# Rev_A.net
KiCad netlist of a schematic drawn in EAGLE
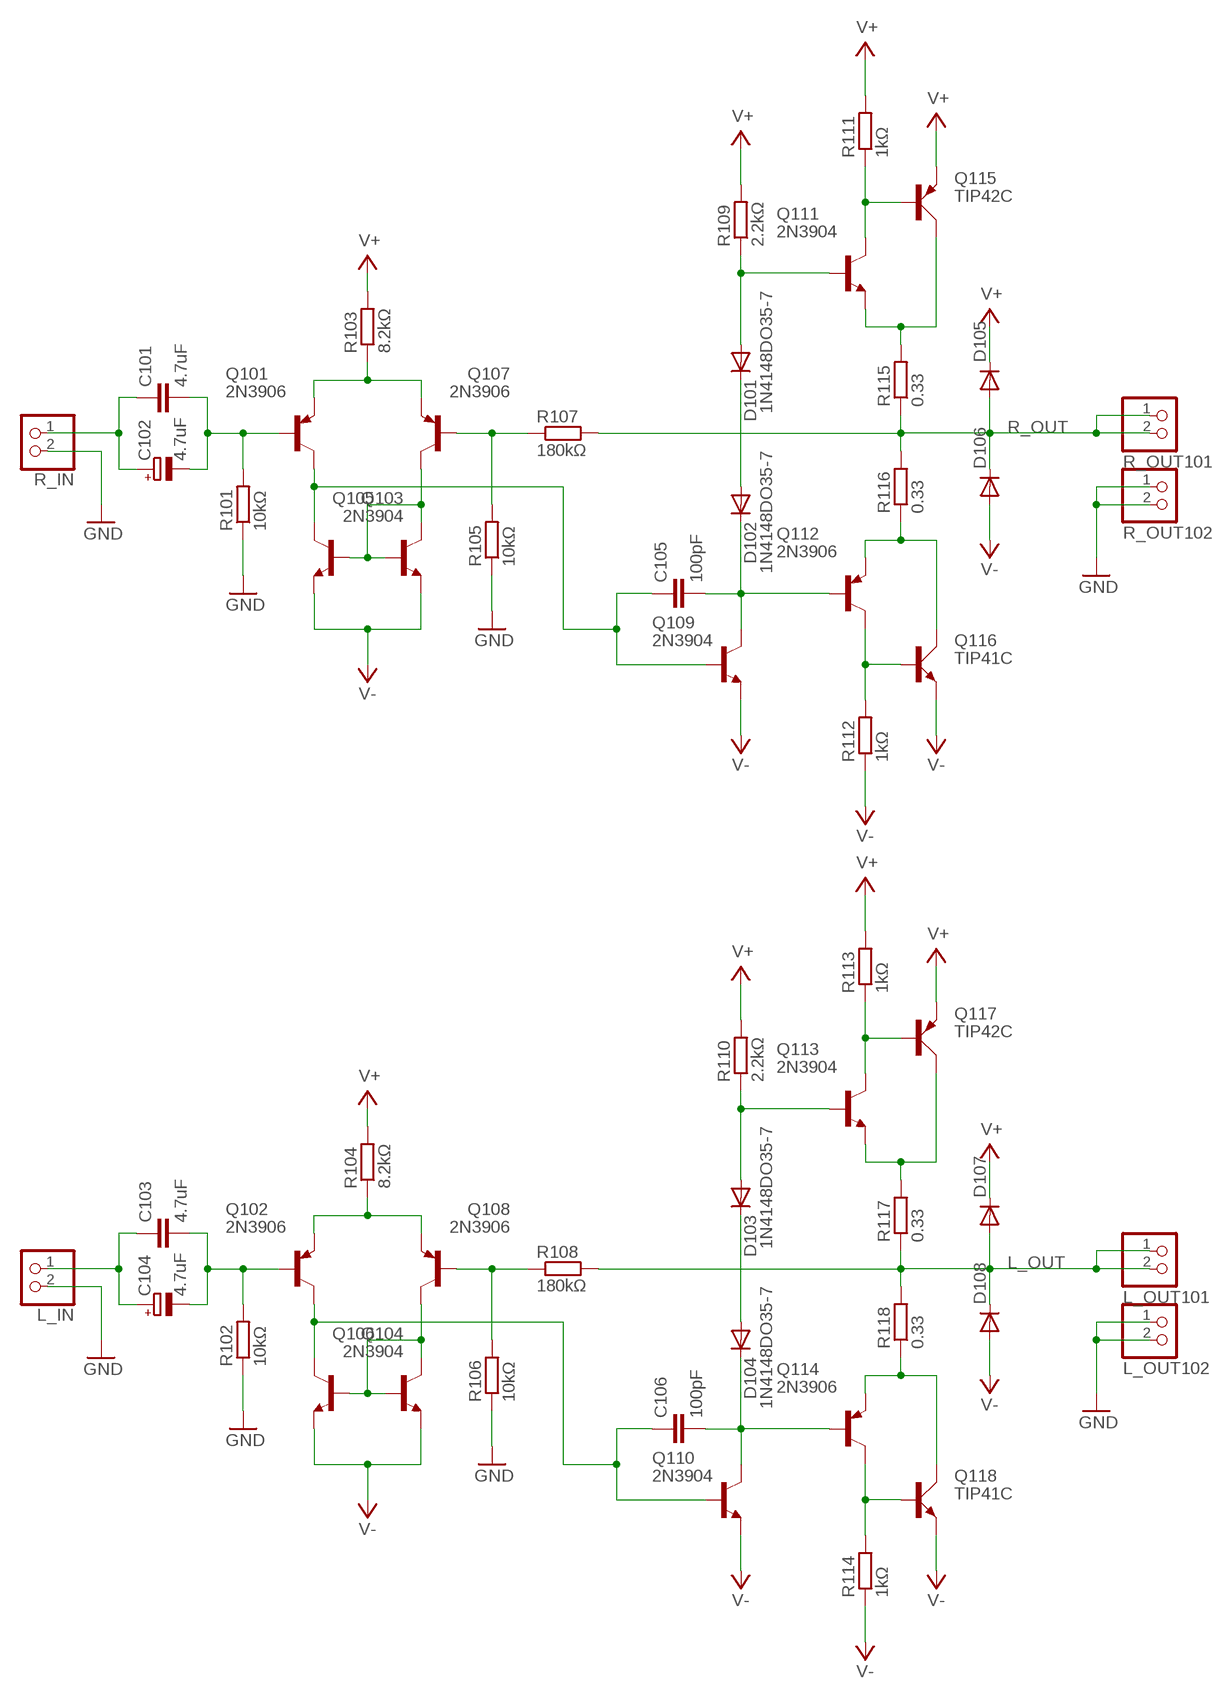
[diagram p0: schematic, sheet 1]
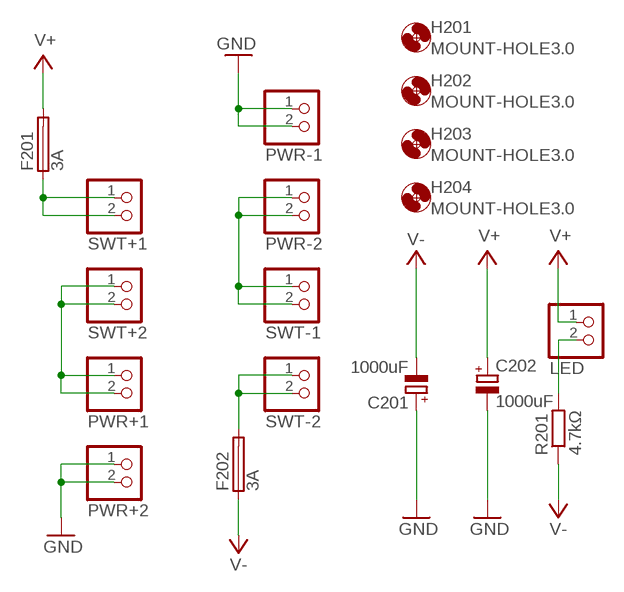
[diagram p1: schematic, sheet 2]

(export (version "E")
  (design (tool "Eeschema 10.0.6"))
  (components
    (comp (ref "C101")
      (value "4.7uF")
      (footprint "eagle-import:C225-113X268")
      (libsource (lib "eagle-import") (part "C-EU225-113X268"))
    )
    (comp (ref "C102")
      (value "4.7uF")
      (footprint "eagle-import:E2-5")
      (libsource (lib "eagle-import") (part "CPOL-EUE2-5"))
    )
    (comp (ref "C103")
      (value "4.7uF")
      (footprint "eagle-import:C225-113X268")
      (libsource (lib "eagle-import") (part "C-EU225-113X268"))
    )
    (comp (ref "C104")
      (value "4.7uF")
      (footprint "eagle-import:E2-5")
      (libsource (lib "eagle-import") (part "CPOL-EUE2-5"))
    )
    (comp (ref "C105")
      (value "100pF")
      (footprint "eagle-import:C050-050X075")
      (libsource (lib "eagle-import") (part "C-EU050-050X075"))
    )
    (comp (ref "C106")
      (value "100pF")
      (footprint "eagle-import:C050-050X075")
      (libsource (lib "eagle-import") (part "C-EU050-050X075"))
    )
    (comp (ref "D101")
      (value "1N4148DO35-7")
      (footprint "eagle-import:DO35-7")
      (libsource (lib "eagle-import") (part "1N4148DO35-7"))
    )
    (comp (ref "D102")
      (value "1N4148DO35-7")
      (footprint "eagle-import:DO35-7")
      (libsource (lib "eagle-import") (part "1N4148DO35-7"))
    )
    (comp (ref "D103")
      (value "1N4148DO35-7")
      (footprint "eagle-import:DO35-7")
      (libsource (lib "eagle-import") (part "1N4148DO35-7"))
    )
    (comp (ref "D104")
      (value "1N4148DO35-7")
      (footprint "eagle-import:DO35-7")
      (libsource (lib "eagle-import") (part "1N4148DO35-7"))
    )
    (comp (ref "D105")
      (value "1N4148DO35-7")
      (footprint "eagle-import:DO35-7")
      (libsource (lib "eagle-import") (part "1N4148DO35-7"))
    )
    (comp (ref "D106")
      (value "1N4148DO35-7")
      (footprint "eagle-import:DO35-7")
      (libsource (lib "eagle-import") (part "1N4148DO35-7"))
    )
    (comp (ref "D107")
      (value "1N4148DO35-7")
      (footprint "eagle-import:DO35-7")
      (libsource (lib "eagle-import") (part "1N4148DO35-7"))
    )
    (comp (ref "D108")
      (value "1N4148DO35-7")
      (footprint "eagle-import:DO35-7")
      (libsource (lib "eagle-import") (part "1N4148DO35-7"))
    )
    (comp (ref "L_IN")
      (value "JST_2PIN-THM")
      (footprint "eagle-import:JST-PH-2-THM")
      (libsource (lib "eagle-import") (part "JST_2PIN-THM"))
    )
    (comp (ref "L_OUT101")
      (value "JST_2PIN-THM")
      (footprint "eagle-import:JST-PH-2-THM")
      (libsource (lib "eagle-import") (part "JST_2PIN-THM"))
    )
    (comp (ref "L_OUT102")
      (value "JST_2PIN-THM")
      (footprint "eagle-import:JST-PH-2-THM")
      (libsource (lib "eagle-import") (part "JST_2PIN-THM"))
    )
    (comp (ref "Q101")
      (value "2N3906")
      (footprint "eagle-import:TO92")
      (libsource (lib "eagle-import") (part "2N3906"))
    )
    (comp (ref "Q102")
      (value "2N3906")
      (footprint "eagle-import:TO92")
      (libsource (lib "eagle-import") (part "2N3906"))
    )
    (comp (ref "Q103")
      (value "2N3904")
      (footprint "eagle-import:TO92")
      (libsource (lib "eagle-import") (part "2N3904"))
    )
    (comp (ref "Q104")
      (value "2N3904")
      (footprint "eagle-import:TO92")
      (libsource (lib "eagle-import") (part "2N3904"))
    )
    (comp (ref "Q105")
      (value "2N3904")
      (footprint "eagle-import:TO92")
      (libsource (lib "eagle-import") (part "2N3904"))
    )
    (comp (ref "Q106")
      (value "2N3904")
      (footprint "eagle-import:TO92")
      (libsource (lib "eagle-import") (part "2N3904"))
    )
    (comp (ref "Q107")
      (value "2N3906")
      (footprint "eagle-import:TO92")
      (libsource (lib "eagle-import") (part "2N3906"))
    )
    (comp (ref "Q108")
      (value "2N3906")
      (footprint "eagle-import:TO92")
      (libsource (lib "eagle-import") (part "2N3906"))
    )
    (comp (ref "Q109")
      (value "2N3904")
      (footprint "eagle-import:TO92")
      (libsource (lib "eagle-import") (part "2N3904"))
    )
    (comp (ref "Q110")
      (value "2N3904")
      (footprint "eagle-import:TO92")
      (libsource (lib "eagle-import") (part "2N3904"))
    )
    (comp (ref "Q111")
      (value "2N3904")
      (footprint "eagle-import:TO92")
      (libsource (lib "eagle-import") (part "2N3904"))
    )
    (comp (ref "Q112")
      (value "2N3906")
      (footprint "eagle-import:TO92")
      (libsource (lib "eagle-import") (part "2N3906"))
    )
    (comp (ref "Q113")
      (value "2N3904")
      (footprint "eagle-import:TO92")
      (libsource (lib "eagle-import") (part "2N3904"))
    )
    (comp (ref "Q114")
      (value "2N3906")
      (footprint "eagle-import:TO92")
      (libsource (lib "eagle-import") (part "2N3906"))
    )
    (comp (ref "Q115")
      (value "TIP42C")
      (footprint "eagle-import:TO220AV")
      (libsource (lib "eagle-import") (part "TIP42C"))
    )
    (comp (ref "Q116")
      (value "TIP41C")
      (footprint "eagle-import:TO220AV")
      (libsource (lib "eagle-import") (part "TIP41C"))
    )
    (comp (ref "Q117")
      (value "TIP42C")
      (footprint "eagle-import:TO220AV")
      (libsource (lib "eagle-import") (part "TIP42C"))
    )
    (comp (ref "Q118")
      (value "TIP41C")
      (footprint "eagle-import:TO220AV")
      (libsource (lib "eagle-import") (part "TIP41C"))
    )
    (comp (ref "R101")
      (value "10kΩ")
      (footprint "eagle-import:0207_10")
      (libsource (lib "eagle-import") (part "R-EU_0207/10"))
    )
    (comp (ref "R102")
      (value "10kΩ")
      (footprint "eagle-import:0207_10")
      (libsource (lib "eagle-import") (part "R-EU_0207/10"))
    )
    (comp (ref "R103")
      (value "8.2kΩ")
      (footprint "eagle-import:0207_10")
      (libsource (lib "eagle-import") (part "R-EU_0207/10"))
    )
    (comp (ref "R104")
      (value "8.2kΩ")
      (footprint "eagle-import:0207_10")
      (libsource (lib "eagle-import") (part "R-EU_0207/10"))
    )
    (comp (ref "R105")
      (value "10kΩ")
      (footprint "eagle-import:0207_10")
      (libsource (lib "eagle-import") (part "R-EU_0207/10"))
    )
    (comp (ref "R106")
      (value "10kΩ")
      (footprint "eagle-import:0207_10")
      (libsource (lib "eagle-import") (part "R-EU_0207/10"))
    )
    (comp (ref "R107")
      (value "180kΩ")
      (footprint "eagle-import:0207_10")
      (libsource (lib "eagle-import") (part "R-EU_0207/10"))
    )
    (comp (ref "R108")
      (value "180kΩ")
      (footprint "eagle-import:0207_10")
      (libsource (lib "eagle-import") (part "R-EU_0207/10"))
    )
    (comp (ref "R109")
      (value "2.2kΩ")
      (footprint "eagle-import:0207_10")
      (libsource (lib "eagle-import") (part "R-EU_0207/10"))
    )
    (comp (ref "R110")
      (value "2.2kΩ")
      (footprint "eagle-import:0207_10")
      (libsource (lib "eagle-import") (part "R-EU_0207/10"))
    )
    (comp (ref "R111")
      (value "1kΩ")
      (footprint "eagle-import:0207_10")
      (libsource (lib "eagle-import") (part "R-EU_0207/10"))
    )
    (comp (ref "R112")
      (value "1kΩ")
      (footprint "eagle-import:0207_10")
      (libsource (lib "eagle-import") (part "R-EU_0207/10"))
    )
    (comp (ref "R113")
      (value "1kΩ")
      (footprint "eagle-import:0207_10")
      (libsource (lib "eagle-import") (part "R-EU_0207/10"))
    )
    (comp (ref "R114")
      (value "1kΩ")
      (footprint "eagle-import:0207_10")
      (libsource (lib "eagle-import") (part "R-EU_0207/10"))
    )
    (comp (ref "R115")
      (value "0.33")
      (footprint "eagle-import:0414_15")
      (libsource (lib "eagle-import") (part "R-EU_0414/15"))
    )
    (comp (ref "R116")
      (value "0.33")
      (footprint "eagle-import:0414_15")
      (libsource (lib "eagle-import") (part "R-EU_0414/15"))
    )
    (comp (ref "R117")
      (value "0.33")
      (footprint "eagle-import:0414_15")
      (libsource (lib "eagle-import") (part "R-EU_0414/15"))
    )
    (comp (ref "R118")
      (value "0.33")
      (footprint "eagle-import:0414_15")
      (libsource (lib "eagle-import") (part "R-EU_0414/15"))
    )
    (comp (ref "R_IN")
      (value "JST_2PIN-THM")
      (footprint "eagle-import:JST-PH-2-THM")
      (libsource (lib "eagle-import") (part "JST_2PIN-THM"))
    )
    (comp (ref "R_OUT101")
      (value "JST_2PIN-THM")
      (footprint "eagle-import:JST-PH-2-THM")
      (libsource (lib "eagle-import") (part "JST_2PIN-THM"))
    )
    (comp (ref "R_OUT102")
      (value "JST_2PIN-THM")
      (footprint "eagle-import:JST-PH-2-THM")
      (libsource (lib "eagle-import") (part "JST_2PIN-THM"))
    )
    (comp (ref "C201")
      (value "1000uF")
      (footprint "eagle-import:E5-10,5")
      (libsource (lib "eagle-import") (part "CPOL-EUE5-10.5"))
    )
    (comp (ref "C202")
      (value "1000uF")
      (footprint "eagle-import:E5-10,5")
      (libsource (lib "eagle-import") (part "CPOL-EUE5-10.5"))
    )
    (comp (ref "F201")
      (value "3A")
      (footprint "eagle-import:SH22,5")
      (fields (field (name "MF") "SCHURTER") (field (name "MPN") "0031.8201"))
      (libsource (lib "eagle-import") (part "SH22,5"))
    )
    (comp (ref "F202")
      (value "3A")
      (footprint "eagle-import:SH22,5")
      (fields (field (name "MF") "SCHURTER") (field (name "MPN") "0031.8201"))
      (libsource (lib "eagle-import") (part "SH22,5"))
    )
    (comp (ref "H201")
      (value "MOUNT-HOLE3.0")
      (footprint "eagle-import:3,0")
      (libsource (lib "eagle-import") (part "MOUNT-HOLE3.0"))
    )
    (comp (ref "H202")
      (value "MOUNT-HOLE3.0")
      (footprint "eagle-import:3,0")
      (libsource (lib "eagle-import") (part "MOUNT-HOLE3.0"))
    )
    (comp (ref "H203")
      (value "MOUNT-HOLE3.0")
      (footprint "eagle-import:3,0")
      (libsource (lib "eagle-import") (part "MOUNT-HOLE3.0"))
    )
    (comp (ref "H204")
      (value "MOUNT-HOLE3.0")
      (footprint "eagle-import:3,0")
      (libsource (lib "eagle-import") (part "MOUNT-HOLE3.0"))
    )
    (comp (ref "LED")
      (value "JST_2PIN-THM")
      (footprint "eagle-import:JST-PH-2-THM")
      (libsource (lib "eagle-import") (part "JST_2PIN-THM"))
    )
    (comp (ref "PWR+1")
      (value "JST_2PIN-THM")
      (footprint "eagle-import:JST-PH-2-THM")
      (libsource (lib "eagle-import") (part "JST_2PIN-THM"))
    )
    (comp (ref "PWR+2")
      (value "JST_2PIN-THM")
      (footprint "eagle-import:JST-PH-2-THM")
      (libsource (lib "eagle-import") (part "JST_2PIN-THM"))
    )
    (comp (ref "PWR-1")
      (value "JST_2PIN-THM")
      (footprint "eagle-import:JST-PH-2-THM")
      (libsource (lib "eagle-import") (part "JST_2PIN-THM"))
    )
    (comp (ref "PWR-2")
      (value "JST_2PIN-THM")
      (footprint "eagle-import:JST-PH-2-THM")
      (libsource (lib "eagle-import") (part "JST_2PIN-THM"))
    )
    (comp (ref "R201")
      (value "4.7kΩ")
      (footprint "eagle-import:0207_10")
      (libsource (lib "eagle-import") (part "R-EU_0207/10"))
    )
    (comp (ref "SWT+1")
      (value "JST_2PIN-THM")
      (footprint "eagle-import:JST-PH-2-THM")
      (libsource (lib "eagle-import") (part "JST_2PIN-THM"))
    )
    (comp (ref "SWT+2")
      (value "JST_2PIN-THM")
      (footprint "eagle-import:JST-PH-2-THM")
      (libsource (lib "eagle-import") (part "JST_2PIN-THM"))
    )
    (comp (ref "SWT-1")
      (value "JST_2PIN-THM")
      (footprint "eagle-import:JST-PH-2-THM")
      (libsource (lib "eagle-import") (part "JST_2PIN-THM"))
    )
    (comp (ref "SWT-2")
      (value "JST_2PIN-THM")
      (footprint "eagle-import:JST-PH-2-THM")
      (libsource (lib "eagle-import") (part "JST_2PIN-THM"))
    )
  )
  (nets
    (net (code "1") (name "GND") (class "Default")
      (node (ref "C201") (pin "+") (pinfunction "+_+") (pintype "passive"))
      (node (ref "C202") (pin "-") (pinfunction "-_-") (pintype "passive"))
      (node (ref "L_IN") (pin "2") (pinfunction "1_2") (pintype "passive"))
      (node (ref "L_OUT102") (pin "1") (pinfunction "2_1") (pintype "passive"))
      (node (ref "L_OUT102") (pin "2") (pinfunction "1_2") (pintype "passive"))
      (node (ref "PWR+2") (pin "1") (pinfunction "2_1") (pintype "passive"))
      (node (ref "PWR+2") (pin "2") (pinfunction "1_2") (pintype "passive"))
      (node (ref "PWR-1") (pin "1") (pinfunction "2_1") (pintype "passive"))
      (node (ref "PWR-1") (pin "2") (pinfunction "1_2") (pintype "passive"))
      (node (ref "R101") (pin "1") (pinfunction "1_1") (pintype "passive"))
      (node (ref "R102") (pin "1") (pinfunction "1_1") (pintype "passive"))
      (node (ref "R105") (pin "1") (pinfunction "1_1") (pintype "passive"))
      (node (ref "R106") (pin "1") (pinfunction "1_1") (pintype "passive"))
      (node (ref "R_IN") (pin "2") (pinfunction "1_2") (pintype "passive"))
      (node (ref "R_OUT102") (pin "1") (pinfunction "2_1") (pintype "passive"))
      (node (ref "R_OUT102") (pin "2") (pinfunction "1_2") (pintype "passive"))
    )
    (net (code "2") (name "L_OUT") (class "Default")
      (node (ref "D107") (pin "A") (pinfunction "A_A") (pintype "passive"))
      (node (ref "D108") (pin "C") (pinfunction "C_C") (pintype "passive"))
      (node (ref "L_OUT101") (pin "1") (pinfunction "2_1") (pintype "passive"))
      (node (ref "L_OUT101") (pin "2") (pinfunction "1_2") (pintype "passive"))
      (node (ref "R108") (pin "2") (pinfunction "2_2") (pintype "passive"))
      (node (ref "R117") (pin "1") (pinfunction "1_1") (pintype "passive"))
      (node (ref "R118") (pin "2") (pinfunction "2_2") (pintype "passive"))
    )
    (net (code "3") (name "Net-(D101-PadC)") (class "Default")
      (node (ref "D101") (pin "C") (pinfunction "C_C") (pintype "passive"))
      (node (ref "D102") (pin "A") (pinfunction "A_A") (pintype "passive"))
    )
    (net (code "4") (name "Net-(D103-PadC)") (class "Default")
      (node (ref "D103") (pin "C") (pinfunction "C_C") (pintype "passive"))
      (node (ref "D104") (pin "A") (pinfunction "A_A") (pintype "passive"))
    )
    (net (code "5") (name "Net-(LED-1)") (class "Default")
      (node (ref "LED") (pin "2") (pinfunction "1_2") (pintype "passive"))
      (node (ref "R201") (pin "2") (pinfunction "2_2") (pintype "passive"))
    )
    (net (code "6") (name "Net-(L_IN-2)") (class "Default")
      (node (ref "C103") (pin "1") (pinfunction "1_1") (pintype "passive"))
      (node (ref "C104") (pin "+") (pinfunction "+_+") (pintype "passive"))
      (node (ref "L_IN") (pin "1") (pinfunction "2_1") (pintype "passive"))
    )
    (net (code "7") (name "Net-(PWR+1-1)") (class "Default")
      (node (ref "PWR+1") (pin "1") (pinfunction "2_1") (pintype "passive"))
      (node (ref "PWR+1") (pin "2") (pinfunction "1_2") (pintype "passive"))
      (node (ref "SWT+2") (pin "1") (pinfunction "2_1") (pintype "passive"))
      (node (ref "SWT+2") (pin "2") (pinfunction "1_2") (pintype "passive"))
    )
    (net (code "8") (name "Net-(PWR-2-1)") (class "Default")
      (node (ref "PWR-2") (pin "1") (pinfunction "2_1") (pintype "passive"))
      (node (ref "PWR-2") (pin "2") (pinfunction "1_2") (pintype "passive"))
      (node (ref "SWT-1") (pin "1") (pinfunction "2_1") (pintype "passive"))
      (node (ref "SWT-1") (pin "2") (pinfunction "1_2") (pintype "passive"))
    )
    (net (code "9") (name "Net-(Q101-B)") (class "Default")
      (node (ref "C101") (pin "2") (pinfunction "2_2") (pintype "passive"))
      (node (ref "C102") (pin "-") (pinfunction "-_-") (pintype "passive"))
      (node (ref "Q101") (pin "2") (pinfunction "B_2") (pintype "passive"))
      (node (ref "R101") (pin "2") (pinfunction "2_2") (pintype "passive"))
    )
    (net (code "10") (name "Net-(Q101-C)") (class "Default")
      (node (ref "C105") (pin "1") (pinfunction "1_1") (pintype "passive"))
      (node (ref "Q101") (pin "1") (pinfunction "C_1") (pintype "passive"))
      (node (ref "Q103") (pin "1") (pinfunction "C_1") (pintype "passive"))
      (node (ref "Q109") (pin "2") (pinfunction "B_2") (pintype "passive"))
    )
    (net (code "11") (name "Net-(Q101-E)") (class "Default")
      (node (ref "Q101") (pin "3") (pinfunction "E_3") (pintype "passive"))
      (node (ref "Q107") (pin "3") (pinfunction "E_3") (pintype "passive"))
      (node (ref "R103") (pin "1") (pinfunction "1_1") (pintype "passive"))
    )
    (net (code "12") (name "Net-(Q102-B)") (class "Default")
      (node (ref "C103") (pin "2") (pinfunction "2_2") (pintype "passive"))
      (node (ref "C104") (pin "-") (pinfunction "-_-") (pintype "passive"))
      (node (ref "Q102") (pin "2") (pinfunction "B_2") (pintype "passive"))
      (node (ref "R102") (pin "2") (pinfunction "2_2") (pintype "passive"))
    )
    (net (code "13") (name "Net-(Q102-C)") (class "Default")
      (node (ref "C106") (pin "1") (pinfunction "1_1") (pintype "passive"))
      (node (ref "Q102") (pin "1") (pinfunction "C_1") (pintype "passive"))
      (node (ref "Q104") (pin "1") (pinfunction "C_1") (pintype "passive"))
      (node (ref "Q110") (pin "2") (pinfunction "B_2") (pintype "passive"))
    )
    (net (code "14") (name "Net-(Q102-E)") (class "Default")
      (node (ref "Q102") (pin "3") (pinfunction "E_3") (pintype "passive"))
      (node (ref "Q108") (pin "3") (pinfunction "E_3") (pintype "passive"))
      (node (ref "R104") (pin "1") (pinfunction "1_1") (pintype "passive"))
    )
    (net (code "15") (name "Net-(Q103-B)") (class "Default")
      (node (ref "Q103") (pin "2") (pinfunction "B_2") (pintype "passive"))
      (node (ref "Q105") (pin "1") (pinfunction "C_1") (pintype "passive"))
      (node (ref "Q105") (pin "2") (pinfunction "B_2") (pintype "passive"))
      (node (ref "Q107") (pin "1") (pinfunction "C_1") (pintype "passive"))
    )
    (net (code "16") (name "Net-(Q104-B)") (class "Default")
      (node (ref "Q104") (pin "2") (pinfunction "B_2") (pintype "passive"))
      (node (ref "Q106") (pin "1") (pinfunction "C_1") (pintype "passive"))
      (node (ref "Q106") (pin "2") (pinfunction "B_2") (pintype "passive"))
      (node (ref "Q108") (pin "1") (pinfunction "C_1") (pintype "passive"))
    )
    (net (code "17") (name "Net-(Q107-B)") (class "Default")
      (node (ref "Q107") (pin "2") (pinfunction "B_2") (pintype "passive"))
      (node (ref "R105") (pin "2") (pinfunction "2_2") (pintype "passive"))
      (node (ref "R107") (pin "1") (pinfunction "1_1") (pintype "passive"))
    )
    (net (code "18") (name "Net-(Q108-B)") (class "Default")
      (node (ref "Q108") (pin "2") (pinfunction "B_2") (pintype "passive"))
      (node (ref "R106") (pin "2") (pinfunction "2_2") (pintype "passive"))
      (node (ref "R108") (pin "1") (pinfunction "1_1") (pintype "passive"))
    )
    (net (code "19") (name "Net-(Q109-C)") (class "Default")
      (node (ref "C105") (pin "2") (pinfunction "2_2") (pintype "passive"))
      (node (ref "D102") (pin "C") (pinfunction "C_C") (pintype "passive"))
      (node (ref "Q109") (pin "1") (pinfunction "C_1") (pintype "passive"))
      (node (ref "Q112") (pin "2") (pinfunction "B_2") (pintype "passive"))
    )
    (net (code "20") (name "Net-(Q110-C)") (class "Default")
      (node (ref "C106") (pin "2") (pinfunction "2_2") (pintype "passive"))
      (node (ref "D104") (pin "C") (pinfunction "C_C") (pintype "passive"))
      (node (ref "Q110") (pin "1") (pinfunction "C_1") (pintype "passive"))
      (node (ref "Q114") (pin "2") (pinfunction "B_2") (pintype "passive"))
    )
    (net (code "21") (name "Net-(Q111-B)") (class "Default")
      (node (ref "D101") (pin "A") (pinfunction "A_A") (pintype "passive"))
      (node (ref "Q111") (pin "2") (pinfunction "B_2") (pintype "passive"))
      (node (ref "R109") (pin "1") (pinfunction "1_1") (pintype "passive"))
    )
    (net (code "22") (name "Net-(Q111-C)") (class "Default")
      (node (ref "Q111") (pin "1") (pinfunction "C_1") (pintype "passive"))
      (node (ref "Q115") (pin "B") (pinfunction "B_B") (pintype "passive"))
      (node (ref "R111") (pin "1") (pinfunction "1_1") (pintype "passive"))
    )
    (net (code "23") (name "Net-(Q111-E)") (class "Default")
      (node (ref "Q111") (pin "3") (pinfunction "E_3") (pintype "passive"))
      (node (ref "Q115") (pin "C") (pinfunction "C_C") (pintype "passive"))
      (node (ref "R115") (pin "2") (pinfunction "2_2") (pintype "passive"))
    )
    (net (code "24") (name "Net-(Q112-C)") (class "Default")
      (node (ref "Q112") (pin "1") (pinfunction "C_1") (pintype "passive"))
      (node (ref "Q116") (pin "B") (pinfunction "B_B") (pintype "passive"))
      (node (ref "R112") (pin "2") (pinfunction "2_2") (pintype "passive"))
    )
    (net (code "25") (name "Net-(Q112-E)") (class "Default")
      (node (ref "Q112") (pin "3") (pinfunction "E_3") (pintype "passive"))
      (node (ref "Q116") (pin "C") (pinfunction "C_C") (pintype "passive"))
      (node (ref "R116") (pin "1") (pinfunction "1_1") (pintype "passive"))
    )
    (net (code "26") (name "Net-(Q113-B)") (class "Default")
      (node (ref "D103") (pin "A") (pinfunction "A_A") (pintype "passive"))
      (node (ref "Q113") (pin "2") (pinfunction "B_2") (pintype "passive"))
      (node (ref "R110") (pin "1") (pinfunction "1_1") (pintype "passive"))
    )
    (net (code "27") (name "Net-(Q113-C)") (class "Default")
      (node (ref "Q113") (pin "1") (pinfunction "C_1") (pintype "passive"))
      (node (ref "Q117") (pin "B") (pinfunction "B_B") (pintype "passive"))
      (node (ref "R113") (pin "1") (pinfunction "1_1") (pintype "passive"))
    )
    (net (code "28") (name "Net-(Q113-E)") (class "Default")
      (node (ref "Q113") (pin "3") (pinfunction "E_3") (pintype "passive"))
      (node (ref "Q117") (pin "C") (pinfunction "C_C") (pintype "passive"))
      (node (ref "R117") (pin "2") (pinfunction "2_2") (pintype "passive"))
    )
    (net (code "29") (name "Net-(Q114-C)") (class "Default")
      (node (ref "Q114") (pin "1") (pinfunction "C_1") (pintype "passive"))
      (node (ref "Q118") (pin "B") (pinfunction "B_B") (pintype "passive"))
      (node (ref "R114") (pin "2") (pinfunction "2_2") (pintype "passive"))
    )
    (net (code "30") (name "Net-(Q114-E)") (class "Default")
      (node (ref "Q114") (pin "3") (pinfunction "E_3") (pintype "passive"))
      (node (ref "Q118") (pin "C") (pinfunction "C_C") (pintype "passive"))
      (node (ref "R118") (pin "1") (pinfunction "1_1") (pintype "passive"))
    )
    (net (code "31") (name "Net-(R_IN-2)") (class "Default")
      (node (ref "C101") (pin "1") (pinfunction "1_1") (pintype "passive"))
      (node (ref "C102") (pin "+") (pinfunction "+_+") (pintype "passive"))
      (node (ref "R_IN") (pin "1") (pinfunction "2_1") (pintype "passive"))
    )
    (net (code "32") (name "Net-(SWT+1-1)") (class "Default")
      (node (ref "F201") (pin "1") (pinfunction "1_1") (pintype "passive"))
      (node (ref "SWT+1") (pin "1") (pinfunction "2_1") (pintype "passive"))
      (node (ref "SWT+1") (pin "2") (pinfunction "1_2") (pintype "passive"))
    )
    (net (code "33") (name "Net-(SWT-2-1)") (class "Default")
      (node (ref "F202") (pin "2") (pinfunction "2_2") (pintype "passive"))
      (node (ref "SWT-2") (pin "1") (pinfunction "2_1") (pintype "passive"))
      (node (ref "SWT-2") (pin "2") (pinfunction "1_2") (pintype "passive"))
    )
    (net (code "34") (name "R_OUT") (class "Default")
      (node (ref "D105") (pin "A") (pinfunction "A_A") (pintype "passive"))
      (node (ref "D106") (pin "C") (pinfunction "C_C") (pintype "passive"))
      (node (ref "R107") (pin "2") (pinfunction "2_2") (pintype "passive"))
      (node (ref "R115") (pin "1") (pinfunction "1_1") (pintype "passive"))
      (node (ref "R116") (pin "2") (pinfunction "2_2") (pintype "passive"))
      (node (ref "R_OUT101") (pin "1") (pinfunction "2_1") (pintype "passive"))
      (node (ref "R_OUT101") (pin "2") (pinfunction "1_2") (pintype "passive"))
    )
    (net (code "35") (name "V+") (class "Default")
      (node (ref "C202") (pin "+") (pinfunction "+_+") (pintype "passive"))
      (node (ref "D105") (pin "C") (pinfunction "C_C") (pintype "passive"))
      (node (ref "D107") (pin "C") (pinfunction "C_C") (pintype "passive"))
      (node (ref "F201") (pin "2") (pinfunction "2_2") (pintype "passive"))
      (node (ref "LED") (pin "1") (pinfunction "2_1") (pintype "passive"))
      (node (ref "Q115") (pin "E") (pinfunction "E_E") (pintype "passive"))
      (node (ref "Q117") (pin "E") (pinfunction "E_E") (pintype "passive"))
      (node (ref "R103") (pin "2") (pinfunction "2_2") (pintype "passive"))
      (node (ref "R104") (pin "2") (pinfunction "2_2") (pintype "passive"))
      (node (ref "R109") (pin "2") (pinfunction "2_2") (pintype "passive"))
      (node (ref "R110") (pin "2") (pinfunction "2_2") (pintype "passive"))
      (node (ref "R111") (pin "2") (pinfunction "2_2") (pintype "passive"))
      (node (ref "R113") (pin "2") (pinfunction "2_2") (pintype "passive"))
    )
    (net (code "36") (name "V-") (class "Default")
      (node (ref "C201") (pin "-") (pinfunction "-_-") (pintype "passive"))
      (node (ref "D106") (pin "A") (pinfunction "A_A") (pintype "passive"))
      (node (ref "D108") (pin "A") (pinfunction "A_A") (pintype "passive"))
      (node (ref "F202") (pin "1") (pinfunction "1_1") (pintype "passive"))
      (node (ref "Q103") (pin "3") (pinfunction "E_3") (pintype "passive"))
      (node (ref "Q104") (pin "3") (pinfunction "E_3") (pintype "passive"))
      (node (ref "Q105") (pin "3") (pinfunction "E_3") (pintype "passive"))
      (node (ref "Q106") (pin "3") (pinfunction "E_3") (pintype "passive"))
      (node (ref "Q109") (pin "3") (pinfunction "E_3") (pintype "passive"))
      (node (ref "Q110") (pin "3") (pinfunction "E_3") (pintype "passive"))
      (node (ref "Q116") (pin "E") (pinfunction "E_E") (pintype "passive"))
      (node (ref "Q118") (pin "E") (pinfunction "E_E") (pintype "passive"))
      (node (ref "R112") (pin "1") (pinfunction "1_1") (pintype "passive"))
      (node (ref "R114") (pin "1") (pinfunction "1_1") (pintype "passive"))
      (node (ref "R201") (pin "1") (pinfunction "1_1") (pintype "passive"))
    )
  )
)
